# 3_-MCU_MAIN.net
KiCad netlist of a schematic drawn in Altium Designer
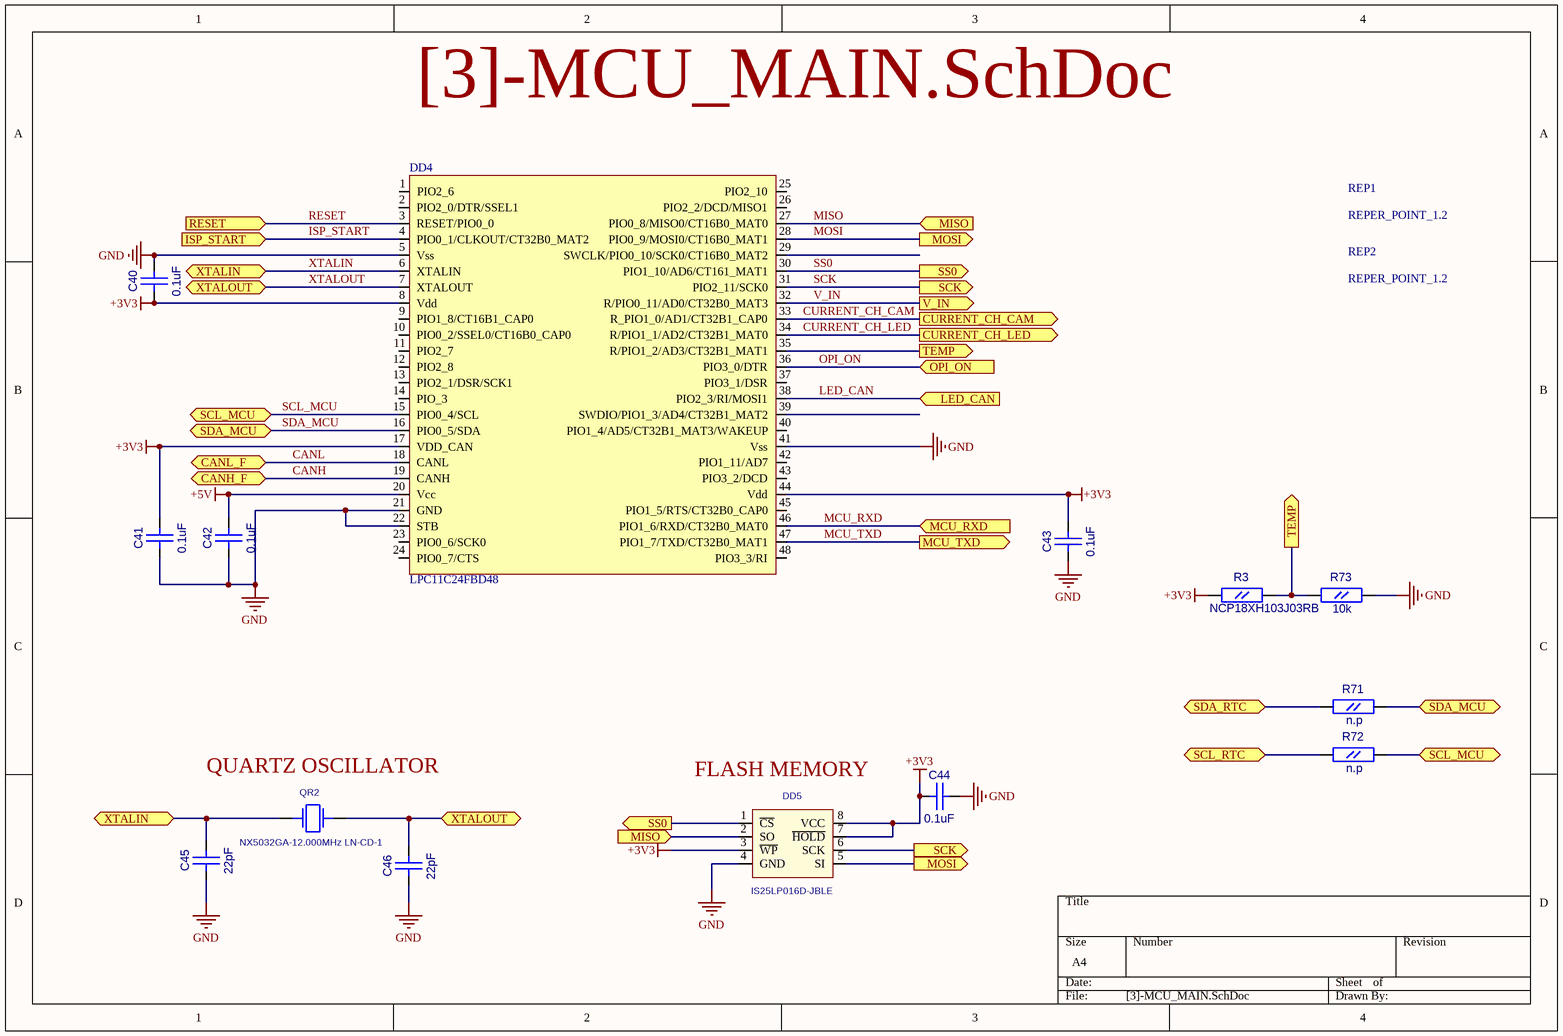
[diagram p0: [3]-MCU_MAIN.SchDoc]

(export (version "E")
  (design (tool "Eeschema 10.0.6"))
  (components
    (comp (ref "C40")
      (value "0.1uF")
      (footprint "CC0603")
      (description "CC0603")
      (libsource (lib "fizik_lib") (part "CC0603"))
    )
    (comp (ref "C41")
      (value "0.1uF")
      (footprint "CC0603")
      (description "CC0603")
      (libsource (lib "fizik_lib") (part "CC0603"))
    )
    (comp (ref "C42")
      (value "0.1uF")
      (footprint "CC0603")
      (description "CC0603")
      (libsource (lib "fizik_lib") (part "CC0603"))
    )
    (comp (ref "C43")
      (value "0.1uF")
      (footprint "CC0603")
      (description "CC0603")
      (libsource (lib "fizik_lib") (part "CC0603"))
    )
    (comp (ref "C44")
      (value "0.1uF")
      (footprint "CC0603")
      (description "CC0603")
      (libsource (lib "gprs_modem_2") (part "CC0603"))
    )
    (comp (ref "C45")
      (value "22pF")
      (footprint "CC0603")
      (description "CC0603")
      (libsource (lib "gprs_modem_2") (part "CC0603"))
    )
    (comp (ref "C46")
      (value "22pF")
      (footprint "CC0603")
      (description "CC0603")
      (libsource (lib "gprs_modem_2") (part "CC0603"))
    )
    (comp (ref "DD4")
      (value "LPC11C24FBD48")
      (footprint "LQFP48")
      (libsource (lib "fizik_lib") (part "LPC11C24FBD48"))
    )
    (comp (ref "DD5")
      (value "IS25LP016D-JBLE")
      (footprint "EIAJ_SO8")
      (description "S25FL016A0LMFI01")
      (libsource (lib "gprs_modem_2") (part "S25FL016A0LMFI01"))
    )
    (comp (ref "QR2")
      (value "NX5032GA-12.000MHz LN-CD-1")
      (footprint "AC5032_2")
      (description "AC5032/2")
      (libsource (lib "gprs_modem_2") (part "AC5032_2"))
    )
    (comp (ref "R3")
      (value "NCP18XH103J03RB")
      (footprint "RC0603")
      (description "RC0603")
      (libsource (lib "fizik_lib") (part "RC0603"))
    )
    (comp (ref "R71")
      (value "n.p")
      (footprint "RC0603")
      (description "RC0603")
      (libsource (lib "fizik_lib") (part "RC0603"))
    )
    (comp (ref "R72")
      (value "n.p")
      (footprint "RC0603")
      (description "RC0603")
      (libsource (lib "fizik_lib") (part "RC0603"))
    )
    (comp (ref "R73")
      (value "10k")
      (footprint "RC0603")
      (description "RC0603")
      (libsource (lib "fizik_lib") (part "RC0603"))
    )
    (comp (ref "REP1")
      (value "REPER_POINT_1.2")
      (footprint "REPER1.2")
      (description "REPER1.2")
      (libsource (lib "fizik_lib") (part "REPER1.2"))
    )
    (comp (ref "REP2")
      (value "REPER_POINT_1.2")
      (footprint "REPER1.2")
      (description "REPER1.2")
      (libsource (lib "fizik_lib") (part "REPER1.2"))
    )
  )
  (nets
    (net (code "1") (name "+3V3") (class "Default")
      (node (ref "C40") (pin "1") (pinfunction "A_1") (pintype "passive"))
      (node (ref "C41") (pin "2") (pinfunction "B_2") (pintype "passive"))
      (node (ref "C43") (pin "2") (pinfunction "B_2") (pintype "passive"))
      (node (ref "C44") (pin "1") (pinfunction "A_1") (pintype "passive"))
      (node (ref "DD4") (pin "17") (pinfunction "VDD_CAN_17") (pintype "passive"))
      (node (ref "DD4") (pin "44") (pinfunction "Vdd_44") (pintype "passive"))
      (node (ref "DD4") (pin "8") (pinfunction "Vdd_8") (pintype "passive"))
      (node (ref "DD5") (pin "3") (pinfunction "~{WP}_3") (pintype "passive"))
      (node (ref "DD5") (pin "7") (pinfunction "~{HOLD}_7") (pintype "passive"))
      (node (ref "DD5") (pin "8") (pinfunction "VCC_8") (pintype "passive"))
      (node (ref "R3") (pin "1") (pinfunction "A_1") (pintype "passive"))
    )
    (net (code "2") (name "+5V") (class "Default")
      (node (ref "C42") (pin "2") (pinfunction "B_2") (pintype "passive"))
      (node (ref "DD4") (pin "20") (pinfunction "Vcc_20") (pintype "passive"))
    )
    (net (code "3") (name "/CANH") (class "Default")
      (node (ref "DD4") (pin "19") (pinfunction "CANH_19") (pintype "passive"))
    )
    (net (code "4") (name "/CANL") (class "Default")
      (node (ref "DD4") (pin "18") (pinfunction "CANL_18") (pintype "passive"))
    )
    (net (code "5") (name "/CURRENT_CH_CAM") (class "Default")
      (node (ref "DD4") (pin "33") (pinfunction "R_PIO1_0/AD1/CT32B1_CAP0_33") (pintype "passive"))
    )
    (net (code "6") (name "/CURRENT_CH_LED") (class "Default")
      (node (ref "DD4") (pin "34") (pinfunction "R/PIO1_1/AD2/CT32B1_MAT0_34") (pintype "passive"))
    )
    (net (code "7") (name "/ISP_START") (class "Default")
      (node (ref "DD4") (pin "4") (pinfunction "PIO0_1/CLKOUT/CT32B0_MAT2_4") (pintype "passive"))
    )
    (net (code "8") (name "/LED_CAN") (class "Default")
      (node (ref "DD4") (pin "38") (pinfunction "PIO2_3/RI/MOSI1_38") (pintype "passive"))
    )
    (net (code "9") (name "/MCU_RXD") (class "Default")
      (node (ref "DD4") (pin "46") (pinfunction "PIO1_6/RXD/CT32B0_MAT0_46") (pintype "passive"))
    )
    (net (code "10") (name "/MCU_TXD") (class "Default")
      (node (ref "DD4") (pin "47") (pinfunction "PIO1_7/TXD/CT32B0_MAT1_47") (pintype "passive"))
    )
    (net (code "11") (name "/MISO") (class "Default")
      (node (ref "DD4") (pin "27") (pinfunction "PIO0_8/MISO0/CT16B0_MAT0_27") (pintype "passive"))
      (node (ref "DD5") (pin "2") (pinfunction "SO_2") (pintype "passive"))
    )
    (net (code "12") (name "/MOSI") (class "Default")
      (node (ref "DD4") (pin "28") (pinfunction "PIO0_9/MOSI0/CT16B0_MAT1_28") (pintype "passive"))
      (node (ref "DD5") (pin "5") (pinfunction "SI_5") (pintype "passive"))
    )
    (net (code "13") (name "/OPI_ON") (class "Default")
      (node (ref "DD4") (pin "36") (pinfunction "PIO3_0/DTR_36") (pintype "passive"))
    )
    (net (code "14") (name "/RESET") (class "Default")
      (node (ref "DD4") (pin "3") (pinfunction "RESET/PIO0_0_3") (pintype "passive"))
    )
    (net (code "15") (name "/SCK") (class "Default")
      (node (ref "DD4") (pin "31") (pinfunction "PIO2_11/SCK0_31") (pintype "passive"))
      (node (ref "DD5") (pin "6") (pinfunction "SCK_6") (pintype "passive"))
    )
    (net (code "16") (name "/SCL_MCU") (class "Default")
      (node (ref "DD4") (pin "15") (pinfunction "PIO0_4/SCL_15") (pintype "passive"))
      (node (ref "R72") (pin "2") (pinfunction "B_2") (pintype "passive"))
    )
    (net (code "17") (name "/SCL_RTC") (class "Default")
      (node (ref "R72") (pin "1") (pinfunction "A_1") (pintype "passive"))
    )
    (net (code "18") (name "/SDA_MCU") (class "Default")
      (node (ref "DD4") (pin "16") (pinfunction "PIO0_5/SDA_16") (pintype "passive"))
      (node (ref "R71") (pin "2") (pinfunction "B_2") (pintype "passive"))
    )
    (net (code "19") (name "/SDA_RTC") (class "Default")
      (node (ref "R71") (pin "1") (pinfunction "A_1") (pintype "passive"))
    )
    (net (code "20") (name "/SS0") (class "Default")
      (node (ref "DD4") (pin "30") (pinfunction "PIO1_10/AD6/CT161_MAT1_30") (pintype "passive"))
      (node (ref "DD5") (pin "1") (pinfunction "~{CS}_1") (pintype "passive"))
    )
    (net (code "21") (name "/TEMP") (class "Default")
      (node (ref "DD4") (pin "35") (pinfunction "R/PIO1_2/AD3/CT32B1_MAT1_35") (pintype "passive"))
      (node (ref "R3") (pin "2") (pinfunction "B_2") (pintype "passive"))
      (node (ref "R73") (pin "1") (pinfunction "A_1") (pintype "passive"))
    )
    (net (code "22") (name "/V_IN") (class "Default")
      (node (ref "DD4") (pin "32") (pinfunction "R/PIO0_11/AD0/CT32B0_MAT3_32") (pintype "passive"))
    )
    (net (code "23") (name "/XTALIN") (class "Default")
      (node (ref "C45") (pin "2") (pinfunction "B_2") (pintype "passive"))
      (node (ref "DD4") (pin "6") (pinfunction "XTALIN_6") (pintype "passive"))
      (node (ref "QR2") (pin "1") (pintype "passive"))
    )
    (net (code "24") (name "/XTALOUT") (class "Default")
      (node (ref "C46") (pin "2") (pinfunction "B_2") (pintype "passive"))
      (node (ref "DD4") (pin "7") (pinfunction "XTALOUT_7") (pintype "passive"))
      (node (ref "QR2") (pin "2") (pintype "passive"))
    )
    (net (code "25") (name "GND") (class "Default")
      (node (ref "C40") (pin "2") (pinfunction "B_2") (pintype "passive"))
      (node (ref "C41") (pin "1") (pinfunction "A_1") (pintype "passive"))
      (node (ref "C42") (pin "1") (pinfunction "A_1") (pintype "passive"))
      (node (ref "C43") (pin "1") (pinfunction "A_1") (pintype "passive"))
      (node (ref "C44") (pin "2") (pinfunction "B_2") (pintype "passive"))
      (node (ref "C45") (pin "1") (pinfunction "A_1") (pintype "passive"))
      (node (ref "C46") (pin "1") (pinfunction "A_1") (pintype "passive"))
      (node (ref "DD4") (pin "21") (pinfunction "GND_21") (pintype "passive"))
      (node (ref "DD4") (pin "22") (pinfunction "STB_22") (pintype "passive"))
      (node (ref "DD4") (pin "41") (pinfunction "Vss_41") (pintype "passive"))
      (node (ref "DD4") (pin "5") (pinfunction "Vss_5") (pintype "passive"))
      (node (ref "DD5") (pin "4") (pinfunction "GND_4") (pintype "passive"))
      (node (ref "R73") (pin "2") (pinfunction "B_2") (pintype "passive"))
    )
    (net (code "26") (name "unconnected-(DD4-PIO0_2{slash}SSEL0{slash}CT16B0_CAP0-Pad10)") (class "Default")
      (node (ref "DD4") (pin "10") (pinfunction "PIO0_2/SSEL0/CT16B0_CAP0_10") (pintype "passive"))
    )
    (net (code "27") (name "unconnected-(DD4-PIO0_6{slash}SCK0-Pad23)") (class "Default")
      (node (ref "DD4") (pin "23") (pinfunction "PIO0_6/SCK0_23") (pintype "passive"))
    )
    (net (code "28") (name "unconnected-(DD4-PIO0_7{slash}CTS-Pad24)") (class "Default")
      (node (ref "DD4") (pin "24") (pinfunction "PIO0_7/CTS_24") (pintype "passive"))
    )
    (net (code "29") (name "unconnected-(DD4-PIO1_4{slash}AD5{slash}CT32B1_MAT3{slash}WAKEUP-Pad40)") (class "Default")
      (node (ref "DD4") (pin "40") (pinfunction "PIO1_4/AD5/CT32B1_MAT3/WAKEUP_40") (pintype "passive"))
    )
    (net (code "30") (name "unconnected-(DD4-PIO1_5{slash}RTS{slash}CT32B0_CAP0-Pad45)") (class "Default")
      (node (ref "DD4") (pin "45") (pinfunction "PIO1_5/RTS/CT32B0_CAP0_45") (pintype "passive"))
    )
    (net (code "31") (name "unconnected-(DD4-PIO1_8{slash}CT16B1_CAP0-Pad9)") (class "Default")
      (node (ref "DD4") (pin "9") (pinfunction "PIO1_8/CT16B1_CAP0_9") (pintype "passive"))
    )
    (net (code "32") (name "unconnected-(DD4-PIO1_11{slash}AD7-Pad42)") (class "Default")
      (node (ref "DD4") (pin "42") (pinfunction "PIO1_11/AD7_42") (pintype "passive"))
    )
    (net (code "33") (name "unconnected-(DD4-PIO2_0{slash}DTR{slash}SSEL1-Pad2)") (class "Default")
      (node (ref "DD4") (pin "2") (pinfunction "PIO2_0/DTR/SSEL1_2") (pintype "passive"))
    )
    (net (code "34") (name "unconnected-(DD4-PIO2_1{slash}DSR{slash}SCK1-Pad13)") (class "Default")
      (node (ref "DD4") (pin "13") (pinfunction "PIO2_1/DSR/SCK1_13") (pintype "passive"))
    )
    (net (code "35") (name "unconnected-(DD4-PIO2_2{slash}DCD{slash}MISO1-Pad26)") (class "Default")
      (node (ref "DD4") (pin "26") (pinfunction "PIO2_2/DCD/MISO1_26") (pintype "passive"))
    )
    (net (code "36") (name "unconnected-(DD4-PIO2_6-Pad1)") (class "Default")
      (node (ref "DD4") (pin "1") (pinfunction "PIO2_6_1") (pintype "passive"))
    )
    (net (code "37") (name "unconnected-(DD4-PIO2_7-Pad11)") (class "Default")
      (node (ref "DD4") (pin "11") (pinfunction "PIO2_7_11") (pintype "passive"))
    )
    (net (code "38") (name "unconnected-(DD4-PIO2_8-Pad12)") (class "Default")
      (node (ref "DD4") (pin "12") (pinfunction "PIO2_8_12") (pintype "passive"))
    )
    (net (code "39") (name "unconnected-(DD4-PIO2_10-Pad25)") (class "Default")
      (node (ref "DD4") (pin "25") (pinfunction "PIO2_10_25") (pintype "passive"))
    )
    (net (code "40") (name "unconnected-(DD4-PIO3_1{slash}DSR-Pad37)") (class "Default")
      (node (ref "DD4") (pin "37") (pinfunction "PIO3_1/DSR_37") (pintype "passive"))
    )
    (net (code "41") (name "unconnected-(DD4-PIO3_2{slash}DCD-Pad43)") (class "Default")
      (node (ref "DD4") (pin "43") (pinfunction "PIO3_2/DCD_43") (pintype "passive"))
    )
    (net (code "42") (name "unconnected-(DD4-PIO3_3{slash}RI-Pad48)") (class "Default")
      (node (ref "DD4") (pin "48") (pinfunction "PIO3_3/RI_48") (pintype "passive"))
    )
    (net (code "43") (name "unconnected-(DD4-PIO_3-Pad14)") (class "Default")
      (node (ref "DD4") (pin "14") (pinfunction "PIO_3_14") (pintype "passive"))
    )
    (net (code "44") (name "unconnected-(DD4-SWCLK{slash}PIO0_10{slash}SCK0{slash}CT16B0_MAT2-Pad29)") (class "Default")
      (node (ref "DD4") (pin "29") (pinfunction "SWCLK/PIO0_10/SCK0/CT16B0_MAT2_29") (pintype "passive"))
    )
    (net (code "45") (name "unconnected-(DD4-SWDIO{slash}PIO1_3{slash}AD4{slash}CT32B1_MAT2-Pad39)") (class "Default")
      (node (ref "DD4") (pin "39") (pinfunction "SWDIO/PIO1_3/AD4/CT32B1_MAT2_39") (pintype "passive"))
    )
    (net (code "46") (name "unconnected-(REP1-Pad1)") (class "Default")
      (node (ref "REP1") (pin "1") (pintype "passive"))
    )
    (net (code "47") (name "unconnected-(REP2-Pad1)") (class "Default")
      (node (ref "REP2") (pin "1") (pintype "passive"))
    )
  )
)
